# Verteilerplatine_MIRZ-MLL-CS-MS.net
KiCad netlist of a schematic drawn in EAGLE
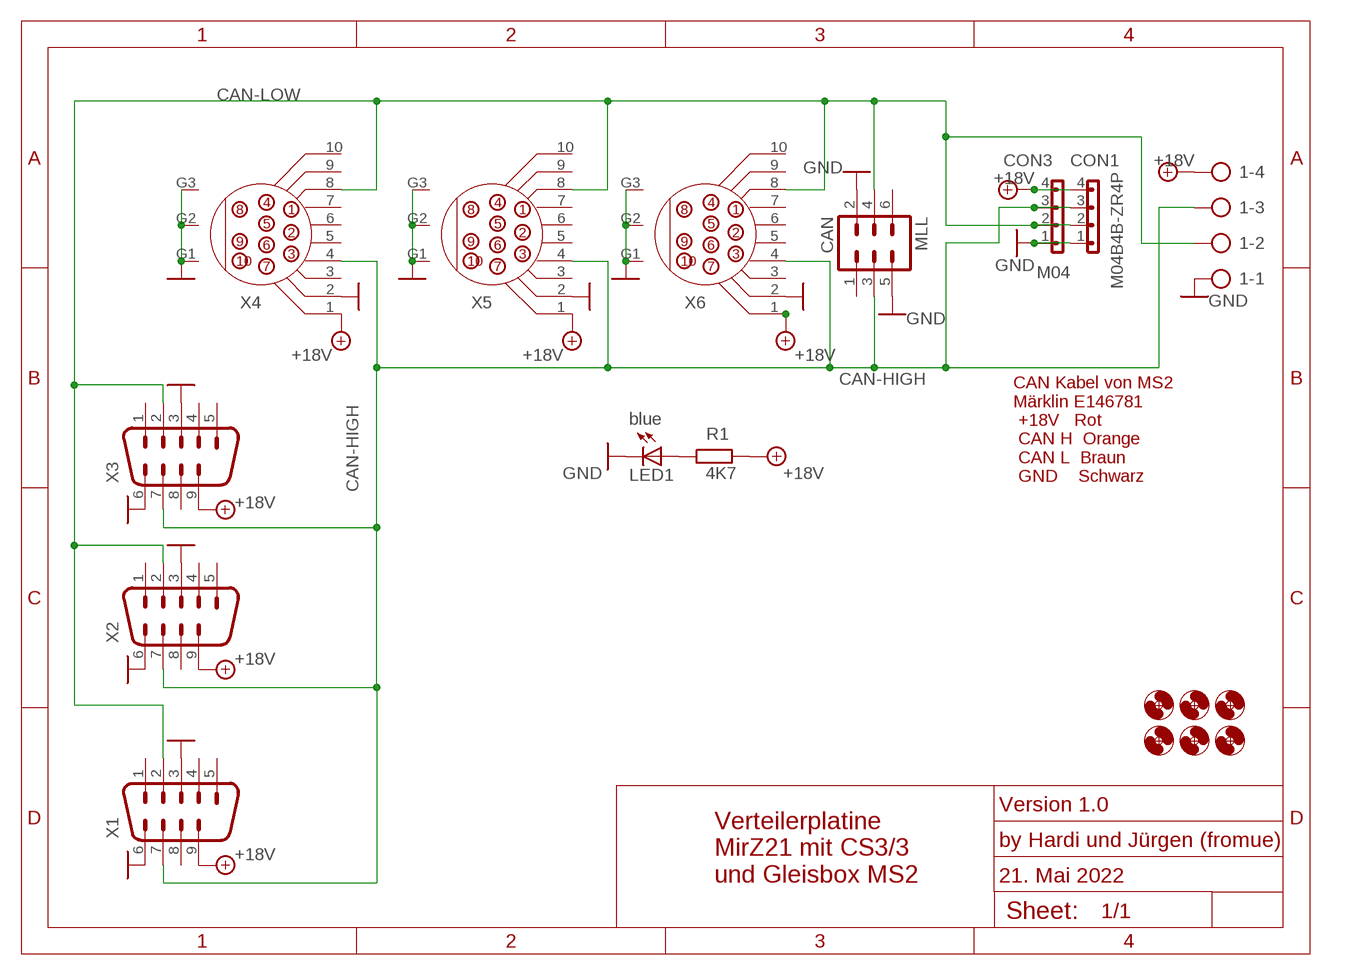
[diagram p0: schematic, sheet 1]

(export (version "E")
  (design (tool "Eeschema 10.0.6"))
  (components
    (comp (ref "1")
      (value "CAN-LOW")
      (footprint "eagle-import:AK500_4-H")
      (libsource (lib "eagle-import") (part "AK500/4-H"))
    )
    (comp (ref "CON1")
      (value "M04B4B-ZR4P")
      (footprint "eagle-import:B4B-ZR4P")
      (libsource (lib "eagle-import") (part "M04B4B-ZR4P"))
    )
    (comp (ref "CON3")
      (value "M04")
      (footprint "eagle-import:1X04")
      (libsource (lib "eagle-import") (part "M04"))
    )
    (comp (ref "H1")
      (value "MOUNT-HOLE3.0")
      (footprint "eagle-import:3,0")
      (libsource (lib "eagle-import") (part "MOUNT-HOLE3.0"))
    )
    (comp (ref "H2")
      (value "MOUNT-HOLE3.0")
      (footprint "eagle-import:3,0")
      (libsource (lib "eagle-import") (part "MOUNT-HOLE3.0"))
    )
    (comp (ref "H3")
      (value "MOUNT-HOLE3.0")
      (footprint "eagle-import:3,0")
      (libsource (lib "eagle-import") (part "MOUNT-HOLE3.0"))
    )
    (comp (ref "H4")
      (value "MOUNT-HOLE3.0")
      (footprint "eagle-import:3,0")
      (libsource (lib "eagle-import") (part "MOUNT-HOLE3.0"))
    )
    (comp (ref "H5")
      (value "MOUNT-HOLE3.0")
      (footprint "eagle-import:3,0")
      (libsource (lib "eagle-import") (part "MOUNT-HOLE3.0"))
    )
    (comp (ref "H6")
      (value "MOUNT-HOLE3.0")
      (footprint "eagle-import:3,0")
      (libsource (lib "eagle-import") (part "MOUNT-HOLE3.0"))
    )
    (comp (ref "LED1")
      (value "blue")
      (footprint "eagle-import:LED3MM")
      (libsource (lib "eagle-import") (part "LED3MM"))
    )
    (comp (ref "MLL")
      (value "CAN")
      (footprint "eagle-import:ML6")
      (libsource (lib "eagle-import") (part "ML6"))
    )
    (comp (ref "R1")
      (value "4K7")
      (footprint "eagle-import:0204_7")
      (libsource (lib "eagle-import") (part "R0204/7"))
    )
    (comp (ref "X1")
      (value "M09V")
      (footprint "eagle-import:M09V")
      (libsource (lib "eagle-import") (part "M09V"))
    )
    (comp (ref "X2")
      (value "M09V")
      (footprint "eagle-import:M09V")
      (libsource (lib "eagle-import") (part "M09V"))
    )
    (comp (ref "X3")
      (value "M09V")
      (footprint "eagle-import:M09V")
      (libsource (lib "eagle-import") (part "M09V"))
    )
    (comp (ref "X4")
      (value "MDSSV-BC10")
      (footprint "eagle-import:SSV-BC10")
      (libsource (lib "eagle-import") (part "MDSSV-BC10"))
    )
    (comp (ref "X5")
      (value "MDSSV-BC10")
      (footprint "eagle-import:SSV-BC10")
      (libsource (lib "eagle-import") (part "MDSSV-BC10"))
    )
    (comp (ref "X6")
      (value "MDSSV-BC10")
      (footprint "eagle-import:SSV-BC10")
      (libsource (lib "eagle-import") (part "MDSSV-BC10"))
    )
  )
  (nets
    (net (code "1") (name "+18V") (class "Default")
      (node (ref "1") (pin "4") (pinfunction "KL_4") (pintype "passive"))
      (node (ref "CON1") (pin "4") (pinfunction "4_4") (pintype "passive"))
      (node (ref "CON3") (pin "4") (pinfunction "4_4") (pintype "passive"))
      (node (ref "R1") (pin "2") (pinfunction "2_2") (pintype "passive"))
      (node (ref "X1") (pin "9") (pinfunction "9_9") (pintype "passive"))
      (node (ref "X2") (pin "9") (pinfunction "9_9") (pintype "passive"))
      (node (ref "X3") (pin "9") (pinfunction "9_9") (pintype "passive"))
      (node (ref "X4") (pin "1") (pinfunction "1_1") (pintype "passive"))
      (node (ref "X5") (pin "1") (pinfunction "1_1") (pintype "passive"))
      (node (ref "X6") (pin "1") (pinfunction "1_1") (pintype "passive"))
    )
    (net (code "2") (name "/CAN-HIGH") (class "Default")
      (node (ref "1") (pin "3") (pinfunction "KL_3") (pintype "passive"))
      (node (ref "CON1") (pin "3") (pinfunction "3_3") (pintype "passive"))
      (node (ref "CON3") (pin "3") (pinfunction "3_3") (pintype "passive"))
      (node (ref "MLL") (pin "3") (pinfunction "3_3") (pintype "passive"))
      (node (ref "X1") (pin "7") (pinfunction "7_7") (pintype "passive"))
      (node (ref "X2") (pin "7") (pinfunction "7_7") (pintype "passive"))
      (node (ref "X3") (pin "7") (pinfunction "7_7") (pintype "passive"))
      (node (ref "X4") (pin "4") (pinfunction "4_4") (pintype "passive"))
      (node (ref "X5") (pin "4") (pinfunction "4_4") (pintype "passive"))
      (node (ref "X6") (pin "4") (pinfunction "4_4") (pintype "passive"))
    )
    (net (code "3") (name "/CAN-LOW") (class "Default")
      (node (ref "1") (pin "2") (pinfunction "KL_2") (pintype "passive"))
      (node (ref "CON1") (pin "2") (pinfunction "2_2") (pintype "passive"))
      (node (ref "CON3") (pin "2") (pinfunction "2_2") (pintype "passive"))
      (node (ref "MLL") (pin "4") (pinfunction "4_4") (pintype "passive"))
      (node (ref "X1") (pin "2") (pinfunction "2_2") (pintype "passive"))
      (node (ref "X2") (pin "2") (pinfunction "2_2") (pintype "passive"))
      (node (ref "X3") (pin "2") (pinfunction "2_2") (pintype "passive"))
      (node (ref "X4") (pin "8") (pinfunction "8_8") (pintype "passive"))
      (node (ref "X5") (pin "8") (pinfunction "8_8") (pintype "passive"))
      (node (ref "X6") (pin "8") (pinfunction "8_8") (pintype "passive"))
    )
    (net (code "4") (name "GND") (class "Default")
      (node (ref "1") (pin "1") (pinfunction "KL_1") (pintype "passive"))
      (node (ref "CON1") (pin "1") (pinfunction "1_1") (pintype "passive"))
      (node (ref "CON3") (pin "1") (pinfunction "1_1") (pintype "passive"))
      (node (ref "LED1") (pin "K") (pinfunction "C_K") (pintype "passive"))
      (node (ref "MLL") (pin "2") (pinfunction "2_2") (pintype "passive"))
      (node (ref "MLL") (pin "5") (pinfunction "5_5") (pintype "passive"))
      (node (ref "X1") (pin "3") (pinfunction "3_3") (pintype "passive"))
      (node (ref "X1") (pin "6") (pinfunction "6_6") (pintype "passive"))
      (node (ref "X2") (pin "3") (pinfunction "3_3") (pintype "passive"))
      (node (ref "X2") (pin "6") (pinfunction "6_6") (pintype "passive"))
      (node (ref "X3") (pin "3") (pinfunction "3_3") (pintype "passive"))
      (node (ref "X3") (pin "6") (pinfunction "6_6") (pintype "passive"))
      (node (ref "X4") (pin "2") (pinfunction "2_2") (pintype "passive"))
      (node (ref "X4") (pin "G1") (pinfunction "GND1_G1") (pintype "passive"))
      (node (ref "X4") (pin "G2") (pinfunction "GND2_G2") (pintype "passive"))
      (node (ref "X4") (pin "G3") (pinfunction "GND3_G3") (pintype "passive"))
      (node (ref "X5") (pin "2") (pinfunction "2_2") (pintype "passive"))
      (node (ref "X5") (pin "G1") (pinfunction "GND1_G1") (pintype "passive"))
      (node (ref "X5") (pin "G2") (pinfunction "GND2_G2") (pintype "passive"))
      (node (ref "X5") (pin "G3") (pinfunction "GND3_G3") (pintype "passive"))
      (node (ref "X6") (pin "2") (pinfunction "2_2") (pintype "passive"))
      (node (ref "X6") (pin "G1") (pinfunction "GND1_G1") (pintype "passive"))
      (node (ref "X6") (pin "G2") (pinfunction "GND2_G2") (pintype "passive"))
      (node (ref "X6") (pin "G3") (pinfunction "GND3_G3") (pintype "passive"))
    )
    (net (code "5") (name "Net-(LED1-PadA)") (class "Default")
      (node (ref "LED1") (pin "A") (pinfunction "A_A") (pintype "passive"))
      (node (ref "R1") (pin "1") (pinfunction "1_1") (pintype "passive"))
    )
    (net (code "6") (name "unconnected-(MLL-Pad1)") (class "Default")
      (node (ref "MLL") (pin "1") (pinfunction "1_1") (pintype "passive"))
    )
    (net (code "7") (name "unconnected-(MLL-Pad6)") (class "Default")
      (node (ref "MLL") (pin "6") (pinfunction "6_6") (pintype "passive"))
    )
    (net (code "8") (name "unconnected-(X1-Pad1)") (class "Default")
      (node (ref "X1") (pin "1") (pinfunction "1_1") (pintype "passive"))
    )
    (net (code "9") (name "unconnected-(X1-Pad4)") (class "Default")
      (node (ref "X1") (pin "4") (pinfunction "4_4") (pintype "passive"))
    )
    (net (code "10") (name "unconnected-(X1-Pad5)") (class "Default")
      (node (ref "X1") (pin "5") (pinfunction "5_5") (pintype "passive"))
    )
    (net (code "11") (name "unconnected-(X1-Pad8)") (class "Default")
      (node (ref "X1") (pin "8") (pinfunction "8_8") (pintype "passive"))
    )
    (net (code "12") (name "unconnected-(X2-Pad1)") (class "Default")
      (node (ref "X2") (pin "1") (pinfunction "1_1") (pintype "passive"))
    )
    (net (code "13") (name "unconnected-(X2-Pad4)") (class "Default")
      (node (ref "X2") (pin "4") (pinfunction "4_4") (pintype "passive"))
    )
    (net (code "14") (name "unconnected-(X2-Pad5)") (class "Default")
      (node (ref "X2") (pin "5") (pinfunction "5_5") (pintype "passive"))
    )
    (net (code "15") (name "unconnected-(X2-Pad8)") (class "Default")
      (node (ref "X2") (pin "8") (pinfunction "8_8") (pintype "passive"))
    )
    (net (code "16") (name "unconnected-(X3-Pad1)") (class "Default")
      (node (ref "X3") (pin "1") (pinfunction "1_1") (pintype "passive"))
    )
    (net (code "17") (name "unconnected-(X3-Pad4)") (class "Default")
      (node (ref "X3") (pin "4") (pinfunction "4_4") (pintype "passive"))
    )
    (net (code "18") (name "unconnected-(X3-Pad5)") (class "Default")
      (node (ref "X3") (pin "5") (pinfunction "5_5") (pintype "passive"))
    )
    (net (code "19") (name "unconnected-(X3-Pad8)") (class "Default")
      (node (ref "X3") (pin "8") (pinfunction "8_8") (pintype "passive"))
    )
    (net (code "20") (name "unconnected-(X4-Pad3)") (class "Default")
      (node (ref "X4") (pin "3") (pinfunction "3_3") (pintype "passive"))
    )
    (net (code "21") (name "unconnected-(X4-Pad5)") (class "Default")
      (node (ref "X4") (pin "5") (pinfunction "5_5") (pintype "passive"))
    )
    (net (code "22") (name "unconnected-(X4-Pad6)") (class "Default")
      (node (ref "X4") (pin "6") (pinfunction "6_6") (pintype "passive"))
    )
    (net (code "23") (name "unconnected-(X4-Pad7)") (class "Default")
      (node (ref "X4") (pin "7") (pinfunction "7_7") (pintype "passive"))
    )
    (net (code "24") (name "unconnected-(X4-Pad9)") (class "Default")
      (node (ref "X4") (pin "9") (pinfunction "9_9") (pintype "passive"))
    )
    (net (code "25") (name "unconnected-(X4-Pad10)") (class "Default")
      (node (ref "X4") (pin "10") (pinfunction "10_10") (pintype "passive"))
    )
    (net (code "26") (name "unconnected-(X5-Pad3)") (class "Default")
      (node (ref "X5") (pin "3") (pinfunction "3_3") (pintype "passive"))
    )
    (net (code "27") (name "unconnected-(X5-Pad5)") (class "Default")
      (node (ref "X5") (pin "5") (pinfunction "5_5") (pintype "passive"))
    )
    (net (code "28") (name "unconnected-(X5-Pad6)") (class "Default")
      (node (ref "X5") (pin "6") (pinfunction "6_6") (pintype "passive"))
    )
    (net (code "29") (name "unconnected-(X5-Pad7)") (class "Default")
      (node (ref "X5") (pin "7") (pinfunction "7_7") (pintype "passive"))
    )
    (net (code "30") (name "unconnected-(X5-Pad9)") (class "Default")
      (node (ref "X5") (pin "9") (pinfunction "9_9") (pintype "passive"))
    )
    (net (code "31") (name "unconnected-(X5-Pad10)") (class "Default")
      (node (ref "X5") (pin "10") (pinfunction "10_10") (pintype "passive"))
    )
    (net (code "32") (name "unconnected-(X6-Pad3)") (class "Default")
      (node (ref "X6") (pin "3") (pinfunction "3_3") (pintype "passive"))
    )
    (net (code "33") (name "unconnected-(X6-Pad5)") (class "Default")
      (node (ref "X6") (pin "5") (pinfunction "5_5") (pintype "passive"))
    )
    (net (code "34") (name "unconnected-(X6-Pad6)") (class "Default")
      (node (ref "X6") (pin "6") (pinfunction "6_6") (pintype "passive"))
    )
    (net (code "35") (name "unconnected-(X6-Pad7)") (class "Default")
      (node (ref "X6") (pin "7") (pinfunction "7_7") (pintype "passive"))
    )
    (net (code "36") (name "unconnected-(X6-Pad9)") (class "Default")
      (node (ref "X6") (pin "9") (pinfunction "9_9") (pintype "passive"))
    )
    (net (code "37") (name "unconnected-(X6-Pad10)") (class "Default")
      (node (ref "X6") (pin "10") (pinfunction "10_10") (pintype "passive"))
    )
  )
)
